# MB_dac.net
KiCad netlist of a schematic drawn in Altium Designer
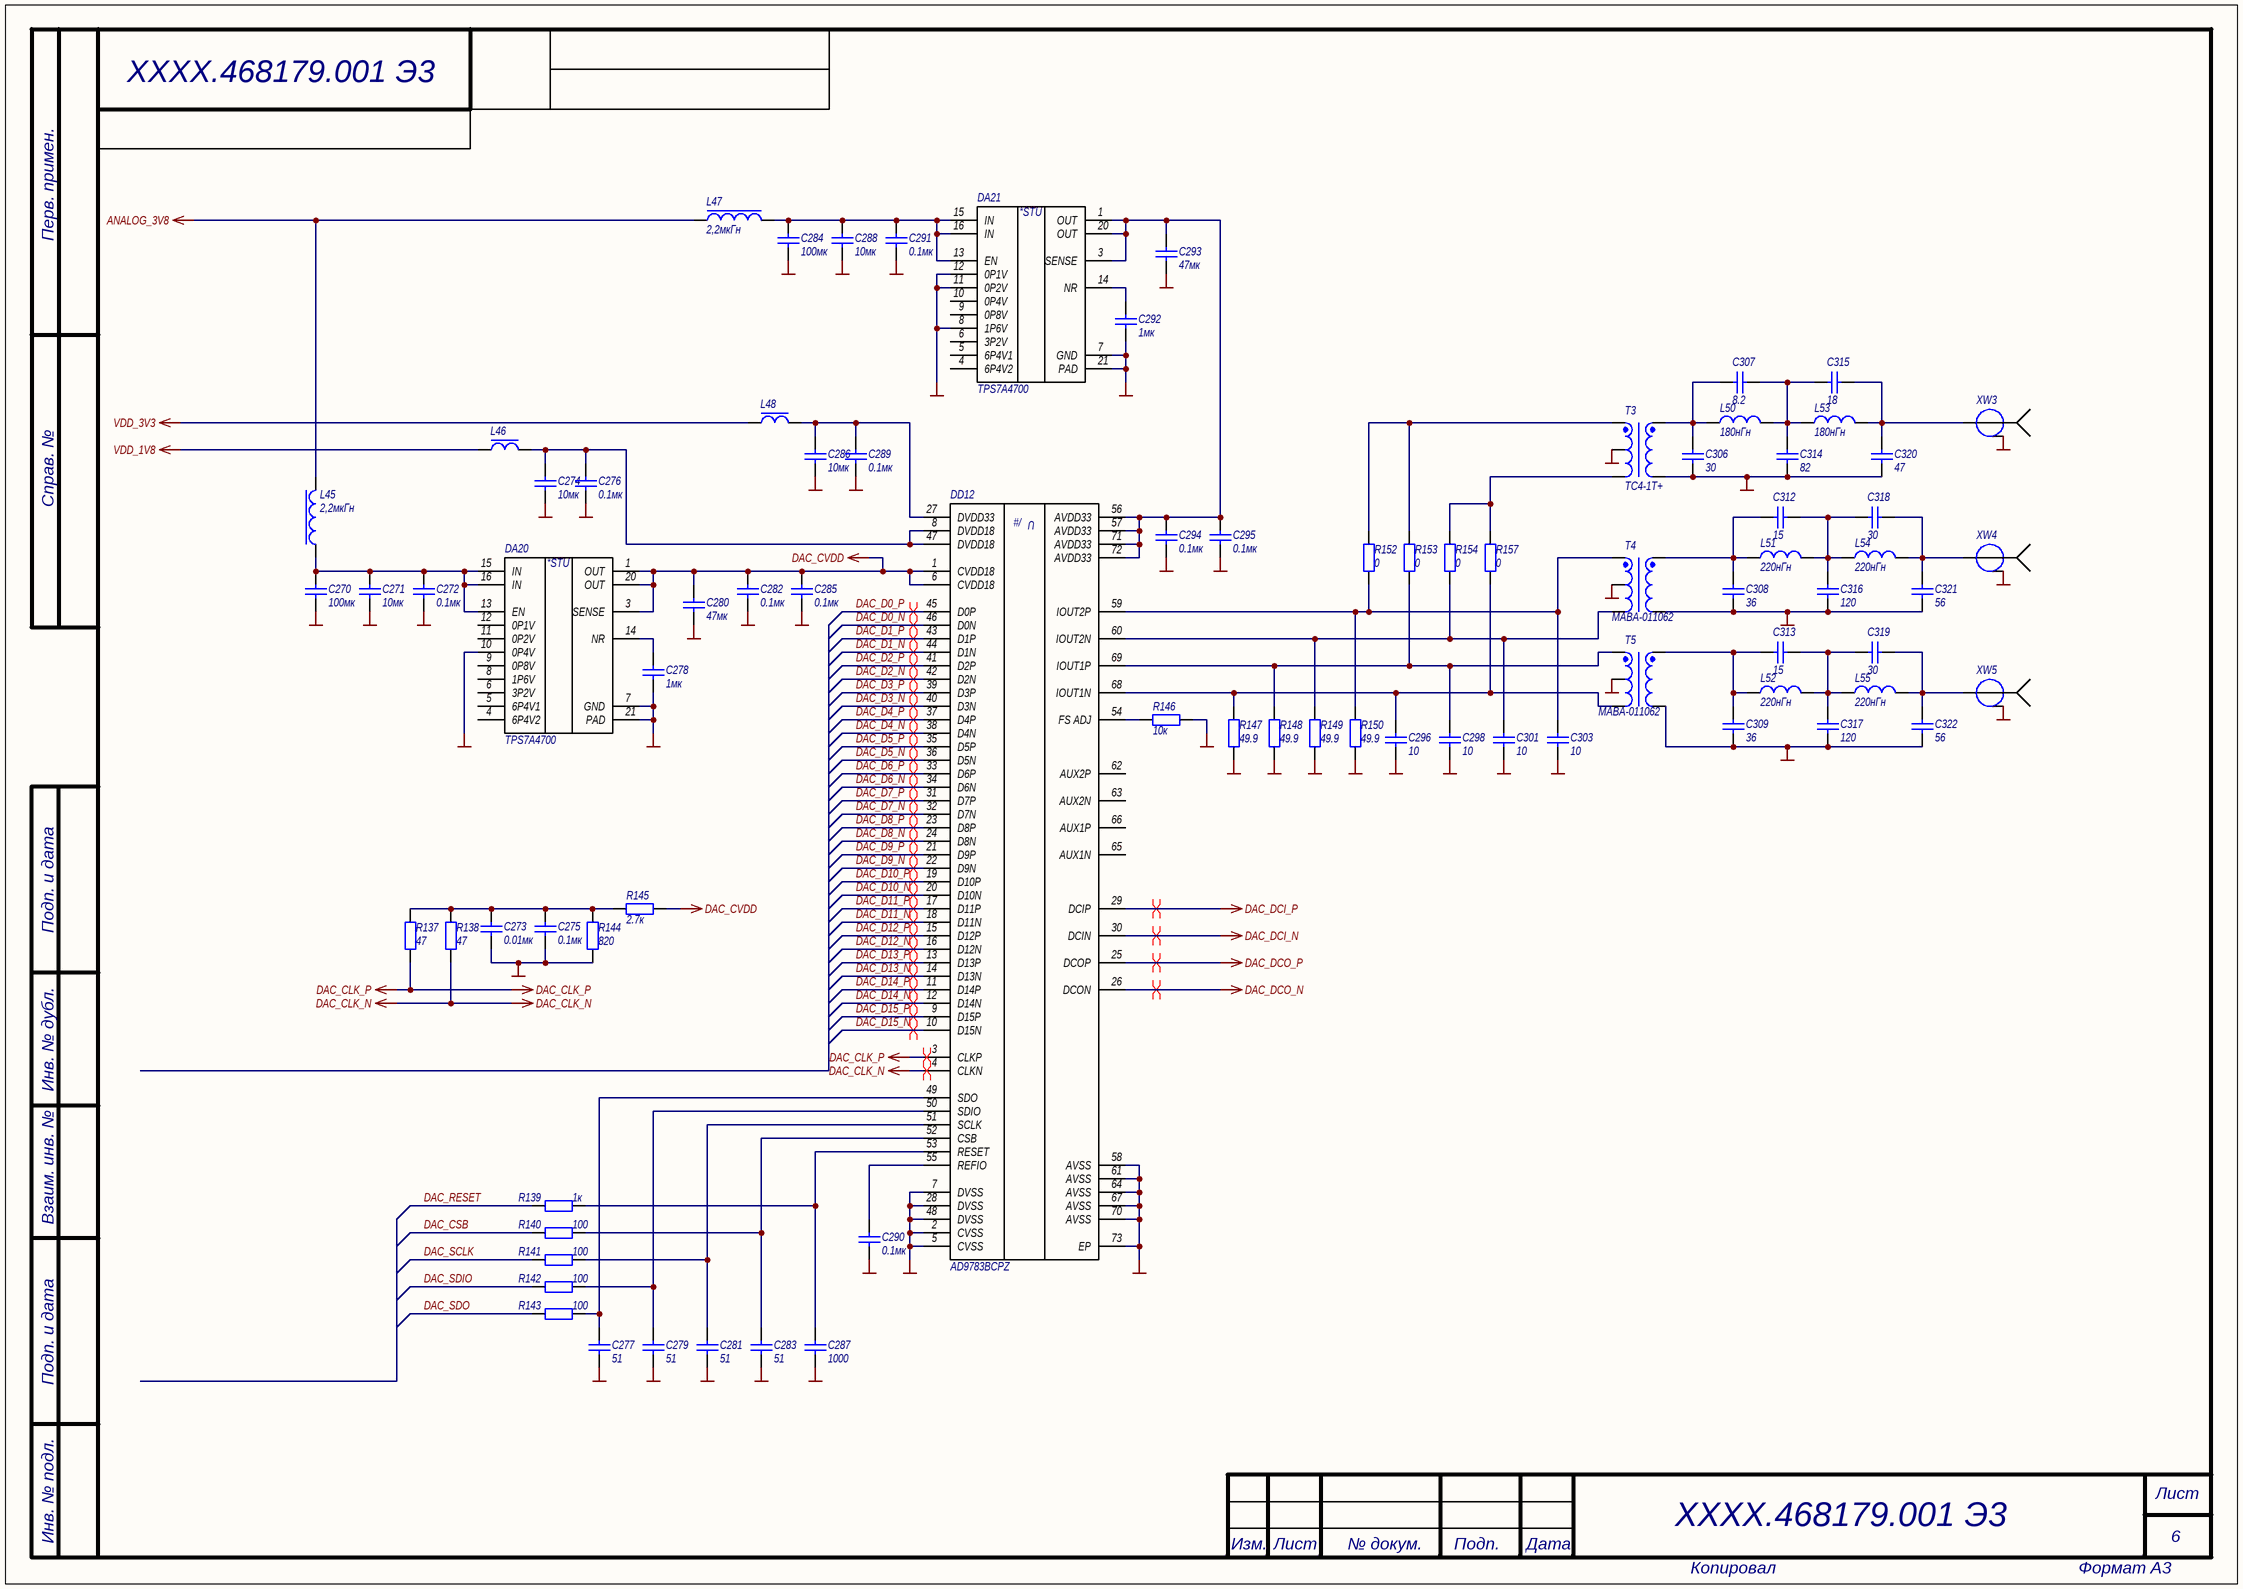
[diagram p0: MB_dac.SchDoc]

(export (version "E")
  (design (tool "Eeschema 10.0.6"))
  (components
    (comp (ref "C270")
      (value "100мк")
      (footprint "CAPC3216X19L")
      (description "Кер. ЧИП-конденсатор")
      (fields (field (name "MANUFACTURER") "Murata") (field (name "TOLERANCE") "±20%"))
      (libsource (lib "nels_caps") (part "Кер.ЧИП конд. 1206 100мкФ X5R 20% 6.3В"))
    )
    (comp (ref "C271")
      (value "10мк")
      (footprint "CAPC1608X08L")
      (description "Кер. ЧИП-конденсатор")
      (fields (field (name "MANUFACTURER") "Murata") (field (name "TOLERANCE") "±20%"))
      (libsource (lib "nels_caps") (part "Кер.ЧИП конд. 0603 10мкФ X5R 20% 6.3В"))
    )
    (comp (ref "C272")
      (value "0.1мк")
      (footprint "CAPC1005X06N")
      (description "Кер. ЧИП-конденсатор")
      (fields (field (name "TOLERANCE") "±10%"))
      (libsource (lib "nels") (part "Кер.ЧИП конд. 0402 0.1мкФ X7R 10%, 16В"))
    )
    (comp (ref "C273")
      (value "0.01мк")
      (footprint "CAPC1005X06N")
      (description "Кер. ЧИП-конденсатор")
      (fields (field (name "TOLERANCE") "±20%"))
      (libsource (lib "nels") (part "Кер.ЧИП конд. 0402 0.01мкФ X7R 10%, 50В"))
    )
    (comp (ref "C274")
      (value "10мк")
      (footprint "CAPC1608X08L")
      (description "Кер. ЧИП-конденсатор")
      (fields (field (name "MANUFACTURER") "Murata") (field (name "TOLERANCE") "±20%"))
      (libsource (lib "nels_caps") (part "Кер.ЧИП конд. 0603 10мкФ X5R 20% 6.3В"))
    )
    (comp (ref "C275")
      (value "0.1мк")
      (footprint "CAPC1005X06N")
      (description "Кер. ЧИП-конденсатор")
      (fields (field (name "TOLERANCE") "±10%"))
      (libsource (lib "nels") (part "Кер.ЧИП конд. 0402 0.1мкФ X7R 10%, 16В"))
    )
    (comp (ref "C276")
      (value "0.1мк")
      (footprint "CAPC1005X06N")
      (description "Кер. ЧИП-конденсатор")
      (fields (field (name "TOLERANCE") "±10%"))
      (libsource (lib "nels") (part "Кер.ЧИП конд. 0402 0.1мкФ X7R 10%, 16В"))
    )
    (comp (ref "C277")
      (value "51")
      (footprint "CAPC1005X06N")
      (description "Кер. ЧИП-конденсатор")
      (fields (field (name "TOLERANCE") "±5%"))
      (libsource (lib "nels") (part "Кер.ЧИП конд. 0402 51пФ NPO 5%, 50В"))
    )
    (comp (ref "C278")
      (value "1мк")
      (footprint "CAPC1005X06N")
      (description "Кер. ЧИП-конденсатор")
      (fields (field (name "TOLERANCE") "±10%"))
      (libsource (lib "nels_caps") (part "Кер.ЧИП конд. 0402 1мкФ X5R 10%, 10В"))
    )
    (comp (ref "C279")
      (value "51")
      (footprint "CAPC1005X06N")
      (description "Кер. ЧИП-конденсатор")
      (fields (field (name "TOLERANCE") "±5%"))
      (libsource (lib "nels") (part "Кер.ЧИП конд. 0402 51пФ NPO 5%, 50В"))
    )
    (comp (ref "C280")
      (value "47мк")
      (footprint "CAPC2012X12L")
      (description "Кер. ЧИП-конденсатор")
      (fields (field (name "MANUFACTURER") "Murata") (field (name "TOLERANCE") "±20%"))
      (libsource (lib "nels_caps") (part "Кер.ЧИП конд. 0805 47мкФ X5R 20% 10В"))
    )
    (comp (ref "C281")
      (value "51")
      (footprint "CAPC1005X06N")
      (description "Кер. ЧИП-конденсатор")
      (fields (field (name "TOLERANCE") "±5%"))
      (libsource (lib "nels") (part "Кер.ЧИП конд. 0402 51пФ NPO 5%, 50В"))
    )
    (comp (ref "C282")
      (value "0.1мк")
      (footprint "CAPC1005X06N")
      (description "Кер. ЧИП-конденсатор")
      (fields (field (name "TOLERANCE") "±10%"))
      (libsource (lib "nels") (part "Кер.ЧИП конд. 0402 0.1мкФ X7R 10%, 16В"))
    )
    (comp (ref "C283")
      (value "51")
      (footprint "CAPC1005X06N")
      (description "Кер. ЧИП-конденсатор")
      (fields (field (name "TOLERANCE") "±5%"))
      (libsource (lib "nels") (part "Кер.ЧИП конд. 0402 51пФ NPO 5%, 50В"))
    )
    (comp (ref "C284")
      (value "100мк")
      (footprint "CAPC3216X19L")
      (description "Кер. ЧИП-конденсатор")
      (fields (field (name "MANUFACTURER") "Murata") (field (name "TOLERANCE") "±20%"))
      (libsource (lib "nels_caps") (part "Кер.ЧИП конд. 1206 100мкФ X5R 20% 6.3В"))
    )
    (comp (ref "C285")
      (value "0.1мк")
      (footprint "CAPC1005X06N")
      (description "Кер. ЧИП-конденсатор")
      (fields (field (name "TOLERANCE") "±10%"))
      (libsource (lib "nels") (part "Кер.ЧИП конд. 0402 0.1мкФ X7R 10%, 16В"))
    )
    (comp (ref "C286")
      (value "10мк")
      (footprint "CAPC1608X08L")
      (description "Кер. ЧИП-конденсатор")
      (fields (field (name "MANUFACTURER") "Murata") (field (name "TOLERANCE") "±20%"))
      (libsource (lib "nels_caps") (part "Кер.ЧИП конд. 0603 10мкФ X5R 20% 6.3В"))
    )
    (comp (ref "C287")
      (value "1000")
      (footprint "CAPC1005X06N")
      (description "Кер. ЧИП-конденсатор")
      (fields (field (name "TOLERANCE") "±5%"))
      (libsource (lib "nels") (part "Кер.ЧИП конд. 0402 1000пФ NP0 5%, 50В"))
    )
    (comp (ref "C288")
      (value "10мк")
      (footprint "CAPC1608X08L")
      (description "Кер. ЧИП-конденсатор")
      (fields (field (name "MANUFACTURER") "Murata") (field (name "TOLERANCE") "±20%"))
      (libsource (lib "nels_caps") (part "Кер.ЧИП конд. 0603 10мкФ X5R 20% 6.3В"))
    )
    (comp (ref "C289")
      (value "0.1мк")
      (footprint "CAPC1005X06N")
      (description "Кер. ЧИП-конденсатор")
      (fields (field (name "TOLERANCE") "±10%"))
      (libsource (lib "nels") (part "Кер.ЧИП конд. 0402 0.1мкФ X7R 10%, 16В"))
    )
    (comp (ref "C290")
      (value "0.1мк")
      (footprint "CAPC1005X06N")
      (description "Кер. ЧИП-конденсатор")
      (fields (field (name "TOLERANCE") "±10%"))
      (libsource (lib "nels") (part "Кер.ЧИП конд. 0402 0.1мкФ X7R 10%, 16В"))
    )
    (comp (ref "C291")
      (value "0.1мк")
      (footprint "CAPC1005X06N")
      (description "Кер. ЧИП-конденсатор")
      (fields (field (name "TOLERANCE") "±10%"))
      (libsource (lib "nels") (part "Кер.ЧИП конд. 0402 0.1мкФ X7R 10%, 16В"))
    )
    (comp (ref "C292")
      (value "1мк")
      (footprint "CAPC1005X06N")
      (description "Кер. ЧИП-конденсатор")
      (fields (field (name "TOLERANCE") "±10%"))
      (libsource (lib "nels_caps") (part "Кер.ЧИП конд. 0402 1мкФ X5R 10%, 10В"))
    )
    (comp (ref "C293")
      (value "47мк")
      (footprint "CAPC2012X12L")
      (description "Кер. ЧИП-конденсатор")
      (fields (field (name "MANUFACTURER") "Murata") (field (name "TOLERANCE") "±20%"))
      (libsource (lib "nels_caps") (part "Кер.ЧИП конд. 0805 47мкФ X5R 20% 10В"))
    )
    (comp (ref "C294")
      (value "0.1мк")
      (footprint "CAPC1005X06N")
      (description "Кер. ЧИП-конденсатор")
      (fields (field (name "TOLERANCE") "±10%"))
      (libsource (lib "nels") (part "Кер.ЧИП конд. 0402 0.1мкФ X7R 10%, 16В"))
    )
    (comp (ref "C295")
      (value "0.1мк")
      (footprint "CAPC1005X06N")
      (description "Кер. ЧИП-конденсатор")
      (fields (field (name "TOLERANCE") "±10%"))
      (libsource (lib "nels") (part "Кер.ЧИП конд. 0402 0.1мкФ X7R 10%, 16В"))
    )
    (comp (ref "C296")
      (value "10")
      (footprint "CAPC1005X06N")
      (description "Кер. ЧИП-конденсатор")
      (fields (field (name "TOLERANCE") "±5%"))
      (libsource (lib "nels_caps") (part "Кер.ЧИП конд. 0402 10пФ NPO 5%, 50В"))
    )
    (comp (ref "C298")
      (value "10")
      (footprint "CAPC1005X06N")
      (description "Кер. ЧИП-конденсатор")
      (fields (field (name "TOLERANCE") "±5%"))
      (libsource (lib "nels_caps") (part "Кер.ЧИП конд. 0402 10пФ NPO 5%, 50В"))
    )
    (comp (ref "C301")
      (value "10")
      (footprint "CAPC1005X06N")
      (description "Кер. ЧИП-конденсатор")
      (fields (field (name "TOLERANCE") "±5%"))
      (libsource (lib "nels_caps") (part "Кер.ЧИП конд. 0402 10пФ NPO 5%, 50В"))
    )
    (comp (ref "C303")
      (value "10")
      (footprint "CAPC1005X06N")
      (description "Кер. ЧИП-конденсатор")
      (fields (field (name "TOLERANCE") "±5%"))
      (libsource (lib "nels_caps") (part "Кер.ЧИП конд. 0402 10пФ NPO 5%, 50В"))
    )
    (comp (ref "C306")
      (value "30")
      (footprint "CAPC1005X06N")
      (description "Кер. ЧИП-конденсатор")
      (fields (field (name "TOLERANCE") "±5%"))
      (libsource (lib "nels_caps") (part "Кер.ЧИП конд. 0402 30пФ NPO 5%, 50В"))
    )
    (comp (ref "C307")
      (value "8.2")
      (footprint "CAPC1005X06N")
      (description "Кер. ЧИП-конденсатор")
      (fields (field (name "TOLERANCE") "±5%"))
      (libsource (lib "nels_caps") (part "Кер.ЧИП конд. 0402 8.2пФ C0G, 50В"))
    )
    (comp (ref "C308")
      (value "36")
      (footprint "CAPC1005X06N")
      (description "Кер. ЧИП-конденсатор")
      (fields (field (name "TOLERANCE") "±5%"))
      (libsource (lib "nels") (part "Кер.ЧИП конд. 0402 36пФ NPO 5%, 50В"))
    )
    (comp (ref "C309")
      (value "36")
      (footprint "CAPC1005X06N")
      (description "Кер. ЧИП-конденсатор")
      (fields (field (name "TOLERANCE") "±5%"))
      (libsource (lib "nels") (part "Кер.ЧИП конд. 0402 36пФ NPO 5%, 50В"))
    )
    (comp (ref "C312")
      (value "15")
      (footprint "CAPC1005X06N")
      (description "Кер. ЧИП-конденсатор")
      (fields (field (name "TOLERANCE") "±5%"))
      (libsource (lib "nels") (part "Кер.ЧИП конд. 0402 15пФ NPO 5%, 50В"))
    )
    (comp (ref "C313")
      (value "15")
      (footprint "CAPC1005X06N")
      (description "Кер. ЧИП-конденсатор")
      (fields (field (name "TOLERANCE") "±5%"))
      (libsource (lib "nels") (part "Кер.ЧИП конд. 0402 15пФ NPO 5%, 50В"))
    )
    (comp (ref "C314")
      (value "82")
      (footprint "CAPC1005X06N")
      (description "Кер. ЧИП-конденсатор")
      (fields (field (name "TOLERANCE") "±5%"))
      (libsource (lib "nels_caps") (part "Кер.ЧИП конд. 0402 82пФ NPO 5%, 50В"))
    )
    (comp (ref "C315")
      (value "18")
      (footprint "CAPC1005X06N")
      (description "Кер. ЧИП-конденсатор")
      (fields (field (name "TOLERANCE") "±5%"))
      (libsource (lib "nels_caps") (part "Кер.ЧИП конд. 0402 18пФ NPO 5%, 50В"))
    )
    (comp (ref "C316")
      (value "120")
      (footprint "CAPC1005X06N")
      (description "Кер. ЧИП-конденсатор")
      (fields (field (name "TOLERANCE") "±5%"))
      (libsource (lib "nels") (part "Кер.ЧИП конд. 0402 120пФ NPO 5%, 50В"))
    )
    (comp (ref "C317")
      (value "120")
      (footprint "CAPC1005X06N")
      (description "Кер. ЧИП-конденсатор")
      (fields (field (name "TOLERANCE") "±5%"))
      (libsource (lib "nels") (part "Кер.ЧИП конд. 0402 120пФ NPO 5%, 50В"))
    )
    (comp (ref "C318")
      (value "30")
      (footprint "CAPC1005X06N")
      (description "Кер. ЧИП-конденсатор")
      (fields (field (name "TOLERANCE") "±5%"))
      (libsource (lib "nels") (part "Кер.ЧИП конд. 0402 30пФ NPO 5%, 50В"))
    )
    (comp (ref "C319")
      (value "30")
      (footprint "CAPC1005X06N")
      (description "Кер. ЧИП-конденсатор")
      (fields (field (name "TOLERANCE") "±5%"))
      (libsource (lib "nels") (part "Кер.ЧИП конд. 0402 30пФ NPO 5%, 50В"))
    )
    (comp (ref "C320")
      (value "47")
      (footprint "CAPC1005X06N")
      (description "Кер. ЧИП-конденсатор")
      (fields (field (name "TOLERANCE") "±5%"))
      (libsource (lib "nels_caps") (part "Кер.ЧИП конд. 0402 47пФ NPO 5%, 50В"))
    )
    (comp (ref "C321")
      (value "56")
      (footprint "CAPC1005X06N")
      (description "Кер. ЧИП-конденсатор")
      (fields (field (name "TOLERANCE") "±5%"))
      (libsource (lib "nels") (part "Кер.ЧИП конд. 0402 56пФ NPO 5%, 50В"))
    )
    (comp (ref "C322")
      (value "56")
      (footprint "CAPC1005X06N")
      (description "Кер. ЧИП-конденсатор")
      (fields (field (name "TOLERANCE") "±5%"))
      (libsource (lib "nels") (part "Кер.ЧИП конд. 0402 56пФ NPO 5%, 50В"))
    )
    (comp (ref "DA20")
      (value "TPS7A4700")
      (footprint "QFN65P500X500X100_HS-21L")
      (description "36-V, 1-A, 4-µVRMS, RF LDO Voltage Regulator")
      (fields (field (name "MANUFACTURER") "TI"))
      (libsource (lib "nels_chip") (part "Микросхема TPS7A4700RGW"))
    )
    (comp (ref "DA21")
      (value "TPS7A4700")
      (footprint "QFN65P500X500X100_HS-21L")
      (description "36-V, 1-A, 4-µVRMS, RF LDO Voltage Regulator")
      (fields (field (name "MANUFACTURER") "TI"))
      (libsource (lib "nels_chip") (part "Микросхема TPS7A4700RGW"))
    )
    (comp (ref "DD12")
      (value "AD9783BCPZ")
      (footprint "LFCSP_VQ_72")
      (description "Dual 12-/14-/16-Bit, LVDS Interface, 500 MSPS DACs")
      (fields (field (name "MANUFACTURER") "AD"))
      (libsource (lib "nels") (part "Микросхема AD9783BCPZ"))
    )
    (comp (ref "L45")
      (value "2,2мкГн")
      (footprint "CSAB0420")
      (description "Molding Power Choke")
      (fields
        (field (name "MANUFACTURER") "Vishay")
        (field (name "MANUFACTURERPARTNUMBER") "IHLP1616ABER1R0M11")
      )
      (libsource (lib "nels_ind") (part "ЧИП индуктивность CSAB0420-2R2M"))
    )
    (comp (ref "L46")
      (value "BLM18PG121SN1D")
      (footprint "INDC1608X08L")
      (description "SMD EMI Suppression Filter EMIFIL")
      (fields (field (name "MANUFACTURER") "Murata"))
      (libsource (lib "nels_ind") (part "ЧИП дроссель 0603 BLM18PG121SN1D"))
    )
    (comp (ref "L47")
      (value "2,2мкГн")
      (footprint "CSAB0420")
      (description "Molding Power Choke")
      (fields
        (field (name "MANUFACTURER") "Vishay")
        (field (name "MANUFACTURERPARTNUMBER") "IHLP1616ABER1R0M11")
      )
      (libsource (lib "nels_ind") (part "ЧИП индуктивность CSAB0420-2R2M"))
    )
    (comp (ref "L48")
      (value "BLM18PG121SN1D")
      (footprint "INDC1608X08L")
      (description "SMD EMI Suppression Filter EMIFIL")
      (fields (field (name "MANUFACTURER") "Murata"))
      (libsource (lib "nels_ind") (part "ЧИП дроссель 0603 BLM18PG121SN1D"))
    )
    (comp (ref "L50")
      (value "180нГн")
      (footprint "INDC0805CS")
      (libsource (lib "nels_ind") (part "ЧИП индуктивность 0805CS-181XGL"))
    )
    (comp (ref "L51")
      (value "220нГн")
      (footprint "INDC0805CS")
      (libsource (lib "nels") (part "ЧИП индуктивность 0805CS-221XGL"))
    )
    (comp (ref "L52")
      (value "220нГн")
      (footprint "INDC0805CS")
      (libsource (lib "nels") (part "ЧИП индуктивность 0805CS-221XGL"))
    )
    (comp (ref "L53")
      (value "180нГн")
      (footprint "INDC0805CS")
      (libsource (lib "nels_ind") (part "ЧИП индуктивность 0805CS-181XGL"))
    )
    (comp (ref "L54")
      (value "220нГн")
      (footprint "INDC0805CS")
      (libsource (lib "nels") (part "ЧИП индуктивность 0805CS-221XGL"))
    )
    (comp (ref "L55")
      (value "220нГн")
      (footprint "INDC0805CS")
      (libsource (lib "nels") (part "ЧИП индуктивность 0805CS-221XGL"))
    )
    (comp (ref "R137")
      (value "47")
      (footprint "RESC1005X06N")
      (description "ЧИП-резистор")
      (fields (field (name "TOLERANCE") "±5%"))
      (libsource (lib "nels") (part "Чип резистор 0402 47 Ом, 5%"))
    )
    (comp (ref "R138")
      (value "47")
      (footprint "RESC1005X06N")
      (description "ЧИП-резистор")
      (fields (field (name "TOLERANCE") "±5%"))
      (libsource (lib "nels") (part "Чип резистор 0402 47 Ом, 5%"))
    )
    (comp (ref "R139")
      (value "1к")
      (footprint "RESC1005X06N")
      (description "ЧИП-резистор")
      (fields (field (name "TOLERANCE") "±5%"))
      (libsource (lib "nels") (part "Чип резистор 0402 1 кОм, 5%"))
    )
    (comp (ref "R140")
      (value "100")
      (footprint "RESC1005X06N")
      (description "ЧИП-резистор")
      (fields (field (name "TOLERANCE") "±5%"))
      (libsource (lib "nels") (part "Чип резистор 0402 100 Ом, 5%"))
    )
    (comp (ref "R141")
      (value "100")
      (footprint "RESC1005X06N")
      (description "ЧИП-резистор")
      (fields (field (name "TOLERANCE") "±5%"))
      (libsource (lib "nels") (part "Чип резистор 0402 100 Ом, 5%"))
    )
    (comp (ref "R142")
      (value "100")
      (footprint "RESC1005X06N")
      (description "ЧИП-резистор")
      (fields (field (name "TOLERANCE") "±5%"))
      (libsource (lib "nels") (part "Чип резистор 0402 100 Ом, 5%"))
    )
    (comp (ref "R143")
      (value "100")
      (footprint "RESC1005X06N")
      (description "ЧИП-резистор")
      (fields (field (name "TOLERANCE") "±5%"))
      (libsource (lib "nels") (part "Чип резистор 0402 100 Ом, 5%"))
    )
    (comp (ref "R144")
      (value "820")
      (footprint "RESC1005X06N")
      (description "ЧИП-резистор")
      (fields (field (name "TOLERANCE") "±5%"))
      (libsource (lib "nels") (part "Чип резистор 0402 820 Ом, 5%"))
    )
    (comp (ref "R145")
      (value "2.7к")
      (footprint "RESC1005X06N")
      (description "ЧИП-резистор")
      (fields (field (name "TOLERANCE") "±5%") (field (name "PUBLISHER") "Altium Limited"))
      (libsource (lib "nels") (part "Чип резистор 0402 2.7 кОм, 5%"))
    )
    (comp (ref "R146")
      (value "10к")
      (footprint "RESC1005X06N")
      (description "ЧИП-резистор")
      (fields (field (name "TOLERANCE") "±5%"))
      (libsource (lib "nels") (part "Чип резистор 0402 10 кОм, 5%"))
    )
    (comp (ref "R147")
      (value "49.9")
      (footprint "RESC1005X06N")
      (description "ЧИП-резистор")
      (fields (field (name "TOLERANCE") "±1%"))
      (libsource (lib "nels") (part "Чип резистор 0402 49,9 Ом, 1%"))
    )
    (comp (ref "R148")
      (value "49.9")
      (footprint "RESC1005X06N")
      (description "ЧИП-резистор")
      (fields (field (name "TOLERANCE") "±1%"))
      (libsource (lib "nels") (part "Чип резистор 0402 49,9 Ом, 1%"))
    )
    (comp (ref "R149")
      (value "49.9")
      (footprint "RESC1005X06N")
      (description "ЧИП-резистор")
      (fields (field (name "TOLERANCE") "±1%"))
      (libsource (lib "nels") (part "Чип резистор 0402 49,9 Ом, 1%"))
    )
    (comp (ref "R150")
      (value "49.9")
      (footprint "RESC1005X06N")
      (description "ЧИП-резистор")
      (fields (field (name "TOLERANCE") "±1%"))
      (libsource (lib "nels") (part "Чип резистор 0402 49,9 Ом, 1%"))
    )
    (comp (ref "R152")
      (value "0")
      (footprint "RESC1005X06N")
      (description "ЧИП-резистор")
      (fields (field (name "TOLERANCE") "±5%"))
      (libsource (lib "nels_res") (part "Чип резистор 0402 0 Ом"))
    )
    (comp (ref "R153")
      (value "0")
      (footprint "RESC1005X06N")
      (description "ЧИП-резистор")
      (fields (field (name "TOLERANCE") "±5%"))
      (libsource (lib "nels_res") (part "Чип резистор 0402 0 Ом"))
    )
    (comp (ref "R154")
      (value "0")
      (footprint "RESC1005X06N")
      (description "ЧИП-резистор")
      (fields (field (name "TOLERANCE") "±5%"))
      (libsource (lib "nels_res") (part "Чип резистор 0402 0 Ом"))
    )
    (comp (ref "R157")
      (value "0")
      (footprint "RESC1005X06N")
      (description "ЧИП-резистор")
      (fields (field (name "TOLERANCE") "±5%"))
      (libsource (lib "nels_res") (part "Чип резистор 0402 0 Ом"))
    )
    (comp (ref "T3")
      (value "TC4-1T+")
      (footprint "SM-22 package")
      (description "RF Transformer 50Ω 0.5 to 300 MHz 1:4")
      (fields (field (name "MANUFACTURER") "minicircuits") (field (name "MANUFACTURERPARTNUMBER") "ADT2-1T+"))
      (libsource (lib "nels_ind") (part "ЧИП трансформатор TC4-1T+"))
    )
    (comp (ref "T4")
      (value "MABA-011062")
      (footprint "SM-22 package")
      (description "1:2 Step up Flux Coupled Balun Transformer 1 – 300 MHz")
      (fields (field (name "MANUFACTURER") "MACOM"))
      (libsource (lib "nels") (part "ЧИП трансформатор MABA-011062"))
    )
    (comp (ref "T5")
      (value "MABA-011062")
      (footprint "SM-22 package")
      (description "1:2 Step up Flux Coupled Balun Transformer 1 – 300 MHz")
      (fields (field (name "MANUFACTURER") "MACOM"))
      (libsource (lib "nels") (part "ЧИП трансформатор MABA-011062"))
    )
    (comp (ref "XW3")
      (value "SMA-JR")
      (footprint "SMA-JR")
      (description "SMA-JR Разъем SMA гнездо на плату, прямой угол")
      (libsource (lib "nels_conn") (part "Соединитель коаксиальный SMA-JR"))
    )
    (comp (ref "XW4")
      (value "SMA-JR")
      (footprint "SMA-JR")
      (description "SMA-JR Разъем SMA гнездо на плату, прямой угол")
      (libsource (lib "nels_conn") (part "Соединитель коаксиальный SMA-JR"))
    )
    (comp (ref "XW5")
      (value "SMA-JR")
      (footprint "SMA-JR")
      (description "SMA-JR Разъем SMA гнездо на плату, прямой угол")
      (libsource (lib "nels_conn") (part "Соединитель коаксиальный SMA-JR"))
    )
  )
  (nets
    (net (code "1") (name "/DAC_CSB") (class "Default")
      (node (ref "R140") (pin "1") (pinfunction "1_1") (pintype "passive"))
    )
    (net (code "2") (name "/DAC_D0_N") (class "Default")
      (node (ref "DD12") (pin "46") (pinfunction "D0N_46") (pintype "passive"))
    )
    (net (code "3") (name "/DAC_D0_P") (class "Default")
      (node (ref "DD12") (pin "45") (pinfunction "D0P_45") (pintype "passive"))
    )
    (net (code "4") (name "/DAC_D1_N") (class "Default")
      (node (ref "DD12") (pin "44") (pinfunction "D1N_44") (pintype "passive"))
    )
    (net (code "5") (name "/DAC_D1_P") (class "Default")
      (node (ref "DD12") (pin "43") (pinfunction "D1P_43") (pintype "passive"))
    )
    (net (code "6") (name "/DAC_D2_N") (class "Default")
      (node (ref "DD12") (pin "42") (pinfunction "D2N_42") (pintype "passive"))
    )
    (net (code "7") (name "/DAC_D2_P") (class "Default")
      (node (ref "DD12") (pin "41") (pinfunction "D2P_41") (pintype "passive"))
    )
    (net (code "8") (name "/DAC_D3_N") (class "Default")
      (node (ref "DD12") (pin "40") (pinfunction "D3N_40") (pintype "passive"))
    )
    (net (code "9") (name "/DAC_D3_P") (class "Default")
      (node (ref "DD12") (pin "39") (pinfunction "D3P_39") (pintype "passive"))
    )
    (net (code "10") (name "/DAC_D4_N") (class "Default")
      (node (ref "DD12") (pin "38") (pinfunction "D4N_38") (pintype "passive"))
    )
    (net (code "11") (name "/DAC_D4_P") (class "Default")
      (node (ref "DD12") (pin "37") (pinfunction "D4P_37") (pintype "passive"))
    )
    (net (code "12") (name "/DAC_D5_N") (class "Default")
      (node (ref "DD12") (pin "36") (pinfunction "D5N_36") (pintype "passive"))
    )
    (net (code "13") (name "/DAC_D5_P") (class "Default")
      (node (ref "DD12") (pin "35") (pinfunction "D5P_35") (pintype "passive"))
    )
    (net (code "14") (name "/DAC_D6_N") (class "Default")
      (node (ref "DD12") (pin "34") (pinfunction "D6N_34") (pintype "passive"))
    )
    (net (code "15") (name "/DAC_D6_P") (class "Default")
      (node (ref "DD12") (pin "33") (pinfunction "D6P_33") (pintype "passive"))
    )
    (net (code "16") (name "/DAC_D7_N") (class "Default")
      (node (ref "DD12") (pin "32") (pinfunction "D7N_32") (pintype "passive"))
    )
    (net (code "17") (name "/DAC_D7_P") (class "Default")
      (node (ref "DD12") (pin "31") (pinfunction "D7P_31") (pintype "passive"))
    )
    (net (code "18") (name "/DAC_D8_N") (class "Default")
      (node (ref "DD12") (pin "24") (pinfunction "D8N_24") (pintype "passive"))
    )
    (net (code "19") (name "/DAC_D8_P") (class "Default")
      (node (ref "DD12") (pin "23") (pinfunction "D8P_23") (pintype "passive"))
    )
    (net (code "20") (name "/DAC_D9_N") (class "Default")
      (node (ref "DD12") (pin "22") (pinfunction "D9N_22") (pintype "passive"))
    )
    (net (code "21") (name "/DAC_D9_P") (class "Default")
      (node (ref "DD12") (pin "21") (pinfunction "D9P_21") (pintype "passive"))
    )
    (net (code "22") (name "/DAC_D10_N") (class "Default")
      (node (ref "DD12") (pin "20") (pinfunction "D10N_20") (pintype "passive"))
    )
    (net (code "23") (name "/DAC_D10_P") (class "Default")
      (node (ref "DD12") (pin "19") (pinfunction "D10P_19") (pintype "passive"))
    )
    (net (code "24") (name "/DAC_D11_N") (class "Default")
      (node (ref "DD12") (pin "18") (pinfunction "D11N_18") (pintype "passive"))
    )
    (net (code "25") (name "/DAC_D11_P") (class "Default")
      (node (ref "DD12") (pin "17") (pinfunction "D11P_17") (pintype "passive"))
    )
    (net (code "26") (name "/DAC_D12_N") (class "Default")
      (node (ref "DD12") (pin "16") (pinfunction "D12N_16") (pintype "passive"))
    )
    (net (code "27") (name "/DAC_D12_P") (class "Default")
      (node (ref "DD12") (pin "15") (pinfunction "D12P_15") (pintype "passive"))
    )
    (net (code "28") (name "/DAC_D13_N") (class "Default")
      (node (ref "DD12") (pin "14") (pinfunction "D13N_14") (pintype "passive"))
    )
    (net (code "29") (name "/DAC_D13_P") (class "Default")
      (node (ref "DD12") (pin "13") (pinfunction "D13P_13") (pintype "passive"))
    )
    (net (code "30") (name "/DAC_D14_N") (class "Default")
      (node (ref "DD12") (pin "12") (pinfunction "D14N_12") (pintype "passive"))
    )
    (net (code "31") (name "/DAC_D14_P") (class "Default")
      (node (ref "DD12") (pin "11") (pinfunction "D14P_11") (pintype "passive"))
    )
    (net (code "32") (name "/DAC_D15_N") (class "Default")
      (node (ref "DD12") (pin "10") (pinfunction "D15N_10") (pintype "passive"))
    )
    (net (code "33") (name "/DAC_D15_P") (class "Default")
      (node (ref "DD12") (pin "9") (pinfunction "D15P_9") (pintype "passive"))
    )
    (net (code "34") (name "/DAC_RESET") (class "Default")
      (node (ref "R139") (pin "1") (pinfunction "1_1") (pintype "passive"))
    )
    (net (code "35") (name "/DAC_SCLK") (class "Default")
      (node (ref "R141") (pin "1") (pinfunction "1_1") (pintype "passive"))
    )
    (net (code "36") (name "/DAC_SDIO") (class "Default")
      (node (ref "R142") (pin "1") (pinfunction "1_1") (pintype "passive"))
    )
    (net (code "37") (name "/DAC_SDO") (class "Default")
      (node (ref "R143") (pin "1") (pinfunction "1_1") (pintype "passive"))
    )
    (net (code "38") (name "ANALOG_3V8") (class "Default")
      (node (ref "L45") (pin "2") (pinfunction "2_2") (pintype "passive"))
      (node (ref "L47") (pin "1") (pinfunction "1_1") (pintype "passive"))
    )
    (net (code "39") (name "DAC_CLK_N") (class "Default")
      (node (ref "DD12") (pin "4") (pinfunction "CLKN_4") (pintype "passive"))
      (node (ref "R138") (pin "2") (pinfunction "2_2") (pintype "passive"))
    )
    (net (code "40") (name "DAC_CLK_P") (class "Default")
      (node (ref "DD12") (pin "3") (pinfunction "CLKP_3") (pintype "passive"))
      (node (ref "R137") (pin "2") (pinfunction "2_2") (pintype "passive"))
    )
    (net (code "41") (name "DAC_CVDD") (class "Default")
      (node (ref "C280") (pin "2") (pinfunction "2_2") (pintype "passive"))
      (node (ref "C282") (pin "2") (pinfunction "2_2") (pintype "passive"))
      (node (ref "C285") (pin "2") (pinfunction "2_2") (pintype "passive"))
      (node (ref "DA20") (pin "1") (pinfunction "OUT_1") (pintype "passive"))
      (node (ref "DA20") (pin "20") (pinfunction "OUT_20") (pintype "passive"))
      (node (ref "DA20") (pin "3") (pinfunction "SENSE_3") (pintype "passive"))
      (node (ref "DD12") (pin "1") (pinfunction "CVDD18_1") (pintype "passive"))
      (node (ref "DD12") (pin "6") (pinfunction "CVDD18_6") (pintype "passive"))
      (node (ref "R145") (pin "2") (pinfunction "2_2") (pintype "passive"))
    )
    (net (code "42") (name "DAC_DCI_N") (class "Default")
      (node (ref "DD12") (pin "30") (pinfunction "DCIN_30") (pintype "passive"))
    )
    (net (code "43") (name "DAC_DCI_P") (class "Default")
      (node (ref "DD12") (pin "29") (pinfunction "DCIP_29") (pintype "passive"))
    )
    (net (code "44") (name "DAC_DCO_N") (class "Default")
      (node (ref "DD12") (pin "26") (pinfunction "DCON_26") (pintype "passive"))
    )
    (net (code "45") (name "DAC_DCO_P") (class "Default")
      (node (ref "DD12") (pin "25") (pinfunction "DCOP_25") (pintype "passive"))
    )
    (net (code "46") (name "GND") (class "Default")
      (node (ref "C270") (pin "1") (pinfunction "1_1") (pintype "passive"))
      (node (ref "C271") (pin "1") (pinfunction "1_1") (pintype "passive"))
      (node (ref "C272") (pin "1") (pinfunction "1_1") (pintype "passive"))
      (node (ref "C273") (pin "1") (pinfunction "1_1") (pintype "passive"))
      (node (ref "C274") (pin "1") (pinfunction "1_1") (pintype "passive"))
      (node (ref "C275") (pin "1") (pinfunction "1_1") (pintype "passive"))
      (node (ref "C276") (pin "1") (pinfunction "1_1") (pintype "passive"))
      (node (ref "C277") (pin "1") (pinfunction "1_1") (pintype "passive"))
      (node (ref "C278") (pin "1") (pinfunction "1_1") (pintype "passive"))
      (node (ref "C279") (pin "1") (pinfunction "1_1") (pintype "passive"))
      (node (ref "C280") (pin "1") (pinfunction "1_1") (pintype "passive"))
      (node (ref "C281") (pin "1") (pinfunction "1_1") (pintype "passive"))
      (node (ref "C282") (pin "1") (pinfunction "1_1") (pintype "passive"))
      (node (ref "C283") (pin "1") (pinfunction "1_1") (pintype "passive"))
      (node (ref "C284") (pin "1") (pinfunction "1_1") (pintype "passive"))
      (node (ref "C285") (pin "1") (pinfunction "1_1") (pintype "passive"))
      (node (ref "C286") (pin "1") (pinfunction "1_1") (pintype "passive"))
      (node (ref "C287") (pin "1") (pinfunction "1_1") (pintype "passive"))
      (node (ref "C288") (pin "1") (pinfunction "1_1") (pintype "passive"))
      (node (ref "C289") (pin "1") (pinfunction "1_1") (pintype "passive"))
      (node (ref "C290") (pin "1") (pinfunction "1_1") (pintype "passive"))
      (node (ref "C291") (pin "1") (pinfunction "1_1") (pintype "passive"))
      (node (ref "C292") (pin "1") (pinfunction "1_1") (pintype "passive"))
      (node (ref "C293") (pin "1") (pinfunction "1_1") (pintype "passive"))
      (node (ref "C294") (pin "1") (pinfunction "1_1") (pintype "passive"))
      (node (ref "C295") (pin "1") (pinfunction "1_1") (pintype "passive"))
      (node (ref "C296") (pin "1") (pinfunction "1_1") (pintype "passive"))
      (node (ref "C298") (pin "1") (pinfunction "1_1") (pintype "passive"))
      (node (ref "C301") (pin "1") (pinfunction "1_1") (pintype "passive"))
      (node (ref "C303") (pin "1") (pinfunction "1_1") (pintype "passive"))
      (node (ref "C306") (pin "1") (pinfunction "1_1") (pintype "passive"))
      (node (ref "C308") (pin "1") (pinfunction "1_1") (pintype "passive"))
      (node (ref "C309") (pin "1") (pinfunction "1_1") (pintype "passive"))
      (node (ref "C314") (pin "1") (pinfunction "1_1") (pintype "passive"))
      (node (ref "C316") (pin "1") (pinfunction "1_1") (pintype "passive"))
      (node (ref "C317") (pin "1") (pinfunction "1_1") (pintype "passive"))
      (node (ref "C320") (pin "1") (pinfunction "1_1") (pintype "passive"))
      (node (ref "C321") (pin "1") (pinfunction "1_1") (pintype "passive"))
      (node (ref "C322") (pin "1") (pinfunction "1_1") (pintype "passive"))
      (node (ref "DA20") (pin "10") (pinfunction "0P4V_10") (pintype "passive"))
      (node (ref "DA20") (pin "21") (pinfunction "PAD_21") (pintype "passive"))
      (node (ref "DA20") (pin "7") (pinfunction "GND_7") (pintype "passive"))
      (node (ref "DA21") (pin "11") (pinfunction "0P2V_11") (pintype "passive"))
      (node (ref "DA21") (pin "12") (pinfunction "0P1V_12") (pintype "passive"))
      (node (ref "DA21") (pin "21") (pinfunction "PAD_21") (pintype "passive"))
      (node (ref "DA21") (pin "7") (pinfunction "GND_7") (pintype "passive"))
      (node (ref "DA21") (pin "8") (pinfunction "1P6V_8") (pintype "passive"))
      (node (ref "DD12") (pin "2") (pinfunction "CVSS_2") (pintype "passive"))
      (node (ref "DD12") (pin "28") (pinfunction "DVSS_28") (pintype "passive"))
      (node (ref "DD12") (pin "48") (pinfunction "DVSS_48") (pintype "passive"))
      (node (ref "DD12") (pin "5") (pinfunction "CVSS_5") (pintype "passive"))
      (node (ref "DD12") (pin "58") (pinfunction "AVSS_58") (pintype "passive"))
      (node (ref "DD12") (pin "61") (pinfunction "AVSS_61") (pintype "passive"))
      (node (ref "DD12") (pin "64") (pinfunction "AVSS_64") (pintype "passive"))
      (node (ref "DD12") (pin "67") (pinfunction "AVSS_67") (pintype "passive"))
      (node (ref "DD12") (pin "7") (pinfunction "DVSS_7") (pintype "passive"))
      (node (ref "DD12") (pin "70") (pinfunction "AVSS_70") (pintype "passive"))
      (node (ref "DD12") (pin "73") (pinfunction "EP_73") (pintype "passive"))
      (node (ref "R144") (pin "2") (pinfunction "2_2") (pintype "passive"))
      (node (ref "R146") (pin "2") (pinfunction "2_2") (pintype "passive"))
      (node (ref "R147") (pin "2") (pinfunction "2_2") (pintype "passive"))
      (node (ref "R148") (pin "2") (pinfunction "2_2") (pintype "passive"))
      (node (ref "R149") (pin "2") (pinfunction "2_2") (pintype "passive"))
      (node (ref "R150") (pin "2") (pinfunction "2_2") (pintype "passive"))
      (node (ref "T3") (pin "2") (pinfunction "SECONARY_CT_2") (pintype "passive"))
      (node (ref "T3") (pin "4") (pinfunction "PRIMARY_4") (pintype "passive"))
      (node (ref "T4") (pin "2") (pinfunction "SECONARY_CT_2") (pintype "passive"))
      (node (ref "T4") (pin "4") (pinfunction "PRIMARY_4") (pintype "passive"))
      (node (ref "T5") (pin "2") (pinfunction "SECONARY_CT_2") (pintype "passive"))
      (node (ref "T5") (pin "4") (pinfunction "PRIMARY_4") (pintype "passive"))
      (node (ref "XW3") (pin "2") (pinfunction "2_2") (pintype "passive"))
      (node (ref "XW4") (pin "2") (pinfunction "2_2") (pintype "passive"))
      (node (ref "XW5") (pin "2") (pinfunction "2_2") (pintype "passive"))
    )
    (net (code "47") (name "Net-(C273-Pad2)") (class "Default")
      (node (ref "C273") (pin "2") (pinfunction "2_2") (pintype "passive"))
      (node (ref "C275") (pin "2") (pinfunction "2_2") (pintype "passive"))
      (node (ref "R137") (pin "1") (pinfunction "1_1") (pintype "passive"))
      (node (ref "R138") (pin "1") (pinfunction "1_1") (pintype "passive"))
      (node (ref "R144") (pin "1") (pinfunction "1_1") (pintype "passive"))
      (node (ref "R145") (pin "1") (pinfunction "1_1") (pintype "passive"))
    )
    (net (code "48") (name "Net-(C274-Pad2)") (class "Default")
      (node (ref "C274") (pin "2") (pinfunction "2_2") (pintype "passive"))
      (node (ref "C276") (pin "2") (pinfunction "2_2") (pintype "passive"))
      (node (ref "DD12") (pin "47") (pinfunction "DVDD18_47") (pintype "passive"))
      (node (ref "DD12") (pin "8") (pinfunction "DVDD18_8") (pintype "passive"))
      (node (ref "L46") (pin "2") (pinfunction "2_2") (pintype "passive"))
    )
    (net (code "49") (name "Net-(C307-Pad1)") (class "Default")
      (node (ref "C307") (pin "1") (pinfunction "1_1") (pintype "passive"))
      (node (ref "C314") (pin "2") (pinfunction "2_2") (pintype "passive"))
      (node (ref "C315") (pin "2") (pinfunction "2_2") (pintype "passive"))
      (node (ref "L50") (pin "2") (pinfunction "2_2") (pintype "passive"))
      (node (ref "L53") (pin "1") (pinfunction "1_1") (pintype "passive"))
    )
    (net (code "50") (name "Net-(C312-Pad1)") (class "Default")
      (node (ref "C312") (pin "1") (pinfunction "1_1") (pintype "passive"))
      (node (ref "C316") (pin "2") (pinfunction "2_2") (pintype "passive"))
      (node (ref "C318") (pin "2") (pinfunction "2_2") (pintype "passive"))
      (node (ref "L51") (pin "2") (pinfunction "2_2") (pintype "passive"))
      (node (ref "L54") (pin "1") (pinfunction "1_1") (pintype "passive"))
    )
    (net (code "51") (name "Net-(C313-Pad1)") (class "Default")
      (node (ref "C313") (pin "1") (pinfunction "1_1") (pintype "passive"))
      (node (ref "C317") (pin "2") (pinfunction "2_2") (pintype "passive"))
      (node (ref "C319") (pin "2") (pinfunction "2_2") (pintype "passive"))
      (node (ref "L52") (pin "2") (pinfunction "2_2") (pintype "passive"))
      (node (ref "L55") (pin "1") (pinfunction "1_1") (pintype "passive"))
    )
    (net (code "52") (name "Net-(C315-Pad1)") (class "Default")
      (node (ref "C315") (pin "1") (pinfunction "1_1") (pintype "passive"))
      (node (ref "C320") (pin "2") (pinfunction "2_2") (pintype "passive"))
      (node (ref "L53") (pin "2") (pinfunction "2_2") (pintype "passive"))
      (node (ref "XW3") (pin "1") (pinfunction "1_1") (pintype "passive"))
    )
    (net (code "53") (name "Net-(C318-Pad1)") (class "Default")
      (node (ref "C318") (pin "1") (pinfunction "1_1") (pintype "passive"))
      (node (ref "C321") (pin "2") (pinfunction "2_2") (pintype "passive"))
      (node (ref "L54") (pin "2") (pinfunction "2_2") (pintype "passive"))
      (node (ref "XW4") (pin "1") (pinfunction "1_1") (pintype "passive"))
    )
    (net (code "54") (name "Net-(C319-Pad1)") (class "Default")
      (node (ref "C319") (pin "1") (pinfunction "1_1") (pintype "passive"))
      (node (ref "C322") (pin "2") (pinfunction "2_2") (pintype "passive"))
      (node (ref "L55") (pin "2") (pinfunction "2_2") (pintype "passive"))
      (node (ref "XW5") (pin "1") (pinfunction "1_1") (pintype "passive"))
    )
    (net (code "55") (name "Net-(DA20-EN)") (class "Default")
      (node (ref "C270") (pin "2") (pinfunction "2_2") (pintype "passive"))
      (node (ref "C271") (pin "2") (pinfunction "2_2") (pintype "passive"))
      (node (ref "C272") (pin "2") (pinfunction "2_2") (pintype "passive"))
      (node (ref "DA20") (pin "13") (pinfunction "EN_13") (pintype "passive"))
      (node (ref "DA20") (pin "15") (pinfunction "IN_15") (pintype "passive"))
      (node (ref "DA20") (pin "16") (pinfunction "IN_16") (pintype "passive"))
      (node (ref "L45") (pin "1") (pinfunction "1_1") (pintype "passive"))
    )
    (net (code "56") (name "Net-(DA20-NR)") (class "Default")
      (node (ref "C278") (pin "2") (pinfunction "2_2") (pintype "passive"))
      (node (ref "DA20") (pin "14") (pinfunction "NR_14") (pintype "passive"))
    )
    (net (code "57") (name "Net-(DA21-EN)") (class "Default")
      (node (ref "C284") (pin "2") (pinfunction "2_2") (pintype "passive"))
      (node (ref "C288") (pin "2") (pinfunction "2_2") (pintype "passive"))
      (node (ref "C291") (pin "2") (pinfunction "2_2") (pintype "passive"))
      (node (ref "DA21") (pin "13") (pinfunction "EN_13") (pintype "passive"))
      (node (ref "DA21") (pin "15") (pinfunction "IN_15") (pintype "passive"))
      (node (ref "DA21") (pin "16") (pinfunction "IN_16") (pintype "passive"))
      (node (ref "L47") (pin "2") (pinfunction "2_2") (pintype "passive"))
    )
    (net (code "58") (name "Net-(DA21-NR)") (class "Default")
      (node (ref "C292") (pin "2") (pinfunction "2_2") (pintype "passive"))
      (node (ref "DA21") (pin "14") (pinfunction "NR_14") (pintype "passive"))
    )
    (net (code "59") (name "Net-(DA21-SENSE)") (class "Default")
      (node (ref "C293") (pin "2") (pinfunction "2_2") (pintype "passive"))
      (node (ref "C294") (pin "2") (pinfunction "2_2") (pintype "passive"))
      (node (ref "C295") (pin "2") (pinfunction "2_2") (pintype "passive"))
      (node (ref "DA21") (pin "1") (pinfunction "OUT_1") (pintype "passive"))
      (node (ref "DA21") (pin "20") (pinfunction "OUT_20") (pintype "passive"))
      (node (ref "DA21") (pin "3") (pinfunction "SENSE_3") (pintype "passive"))
      (node (ref "DD12") (pin "56") (pinfunction "AVDD33_56") (pintype "passive"))
      (node (ref "DD12") (pin "57") (pinfunction "AVDD33_57") (pintype "passive"))
      (node (ref "DD12") (pin "71") (pinfunction "AVDD33_71") (pintype "passive"))
      (node (ref "DD12") (pin "72") (pinfunction "AVDD33_72") (pintype "passive"))
    )
    (net (code "60") (name "Net-(DD12-CSB)") (class "Default")
      (node (ref "C283") (pin "2") (pinfunction "2_2") (pintype "passive"))
      (node (ref "DD12") (pin "52") (pinfunction "CSB_52") (pintype "passive"))
      (node (ref "R140") (pin "2") (pinfunction "2_2") (pintype "passive"))
    )
    (net (code "61") (name "Net-(DD12-DVDD33)") (class "Default")
      (node (ref "C286") (pin "2") (pinfunction "2_2") (pintype "passive"))
      (node (ref "C289") (pin "2") (pinfunction "2_2") (pintype "passive"))
      (node (ref "DD12") (pin "27") (pinfunction "DVDD33_27") (pintype "passive"))
      (node (ref "L48") (pin "2") (pinfunction "2_2") (pintype "passive"))
    )
    (net (code "62") (name "Net-(DD12-FS_ADJ)") (class "Default")
      (node (ref "DD12") (pin "54") (pinfunction "FS_ADJ_54") (pintype "passive"))
      (node (ref "R146") (pin "1") (pinfunction "1_1") (pintype "passive"))
    )
    (net (code "63") (name "Net-(DD12-IOUT1N)") (class "Default")
      (node (ref "C296") (pin "2") (pinfunction "2_2") (pintype "passive"))
      (node (ref "DD12") (pin "68") (pinfunction "IOUT1N_68") (pintype "passive"))
      (node (ref "R147") (pin "1") (pinfunction "1_1") (pintype "passive"))
      (node (ref "R157") (pin "2") (pinfunction "2_2") (pintype "passive"))
      (node (ref "T5") (pin "3") (pinfunction "SECONDARY_3") (pintype "passive"))
    )
    (net (code "64") (name "Net-(DD12-IOUT1P)") (class "Default")
      (node (ref "C298") (pin "2") (pinfunction "2_2") (pintype "passive"))
      (node (ref "DD12") (pin "69") (pinfunction "IOUT1P_69") (pintype "passive"))
      (node (ref "R148") (pin "1") (pinfunction "1_1") (pintype "passive"))
      (node (ref "R153") (pin "2") (pinfunction "2_2") (pintype "passive"))
      (node (ref "T5") (pin "1") (pinfunction "SECONDARY_DOT_1") (pintype "passive"))
    )
    (net (code "65") (name "Net-(DD12-IOUT2N)") (class "Default")
      (node (ref "C301") (pin "2") (pinfunction "2_2") (pintype "passive"))
      (node (ref "DD12") (pin "60") (pinfunction "IOUT2N_60") (pintype "passive"))
      (node (ref "R149") (pin "1") (pinfunction "1_1") (pintype "passive"))
      (node (ref "R154") (pin "2") (pinfunction "2_2") (pintype "passive"))
      (node (ref "T4") (pin "3") (pinfunction "SECONDARY_3") (pintype "passive"))
    )
    (net (code "66") (name "Net-(DD12-IOUT2P)") (class "Default")
      (node (ref "C303") (pin "2") (pinfunction "2_2") (pintype "passive"))
      (node (ref "DD12") (pin "59") (pinfunction "IOUT2P_59") (pintype "passive"))
      (node (ref "R150") (pin "1") (pinfunction "1_1") (pintype "passive"))
      (node (ref "R152") (pin "2") (pinfunction "2_2") (pintype "passive"))
      (node (ref "T4") (pin "1") (pinfunction "SECONDARY_DOT_1") (pintype "passive"))
    )
    (net (code "67") (name "Net-(DD12-REFIO)") (class "Default")
      (node (ref "C290") (pin "2") (pinfunction "2_2") (pintype "passive"))
      (node (ref "DD12") (pin "55") (pinfunction "REFIO_55") (pintype "passive"))
    )
    (net (code "68") (name "Net-(DD12-RESET)") (class "Default")
      (node (ref "C287") (pin "2") (pinfunction "2_2") (pintype "passive"))
      (node (ref "DD12") (pin "53") (pinfunction "RESET_53") (pintype "passive"))
      (node (ref "R139") (pin "2") (pinfunction "2_2") (pintype "passive"))
    )
    (net (code "69") (name "Net-(DD12-SCLK)") (class "Default")
      (node (ref "C281") (pin "2") (pinfunction "2_2") (pintype "passive"))
      (node (ref "DD12") (pin "51") (pinfunction "SCLK_51") (pintype "passive"))
      (node (ref "R141") (pin "2") (pinfunction "2_2") (pintype "passive"))
    )
    (net (code "70") (name "Net-(DD12-SDIO)") (class "Default")
      (node (ref "C279") (pin "2") (pinfunction "2_2") (pintype "passive"))
      (node (ref "DD12") (pin "50") (pinfunction "SDIO_50") (pintype "passive"))
      (node (ref "R142") (pin "2") (pinfunction "2_2") (pintype "passive"))
    )
    (net (code "71") (name "Net-(DD12-SDO)") (class "Default")
      (node (ref "C277") (pin "2") (pinfunction "2_2") (pintype "passive"))
      (node (ref "DD12") (pin "49") (pinfunction "SDO_49") (pintype "passive"))
      (node (ref "R143") (pin "2") (pinfunction "2_2") (pintype "passive"))
    )
    (net (code "72") (name "Net-(T3-PRIMARY_DOT)") (class "Default")
      (node (ref "C306") (pin "2") (pinfunction "2_2") (pintype "passive"))
      (node (ref "C307") (pin "2") (pinfunction "2_2") (pintype "passive"))
      (node (ref "L50") (pin "1") (pinfunction "1_1") (pintype "passive"))
      (node (ref "T3") (pin "5") (pinfunction "PRIMARY_DOT_5") (pintype "passive"))
    )
    (net (code "73") (name "Net-(T3-SECONDARY)") (class "Default")
      (node (ref "R154") (pin "1") (pinfunction "1_1") (pintype "passive"))
      (node (ref "R157") (pin "1") (pinfunction "1_1") (pintype "passive"))
      (node (ref "T3") (pin "3") (pinfunction "SECONDARY_3") (pintype "passive"))
    )
    (net (code "74") (name "Net-(T3-SECONDARY_DOT)") (class "Default")
      (node (ref "R152") (pin "1") (pinfunction "1_1") (pintype "passive"))
      (node (ref "R153") (pin "1") (pinfunction "1_1") (pintype "passive"))
      (node (ref "T3") (pin "1") (pinfunction "SECONDARY_DOT_1") (pintype "passive"))
    )
    (net (code "75") (name "Net-(T4-PRIMARY_DOT)") (class "Default")
      (node (ref "C308") (pin "2") (pinfunction "2_2") (pintype "passive"))
      (node (ref "C312") (pin "2") (pinfunction "2_2") (pintype "passive"))
      (node (ref "L51") (pin "1") (pinfunction "1_1") (pintype "passive"))
      (node (ref "T4") (pin "5") (pinfunction "PRIMARY_DOT_5") (pintype "passive"))
    )
    (net (code "76") (name "Net-(T5-PRIMARY_DOT)") (class "Default")
      (node (ref "C309") (pin "2") (pinfunction "2_2") (pintype "passive"))
      (node (ref "C313") (pin "2") (pinfunction "2_2") (pintype "passive"))
      (node (ref "L52") (pin "1") (pinfunction "1_1") (pintype "passive"))
      (node (ref "T5") (pin "5") (pinfunction "PRIMARY_DOT_5") (pintype "passive"))
    )
    (net (code "77") (name "VDD_1V8") (class "Default")
      (node (ref "L46") (pin "1") (pinfunction "1_1") (pintype "passive"))
    )
    (net (code "78") (name "VDD_3V3") (class "Default")
      (node (ref "L48") (pin "1") (pinfunction "1_1") (pintype "passive"))
    )
    (net (code "79") (name "unconnected-(DA20-0P1V-Pad12)") (class "Default")
      (node (ref "DA20") (pin "12") (pinfunction "0P1V_12") (pintype "passive"))
    )
    (net (code "80") (name "unconnected-(DA20-0P2V-Pad11)") (class "Default")
      (node (ref "DA20") (pin "11") (pinfunction "0P2V_11") (pintype "passive"))
    )
    (net (code "81") (name "unconnected-(DA20-0P8V-Pad9)") (class "Default")
      (node (ref "DA20") (pin "9") (pinfunction "0P8V_9") (pintype "passive"))
    )
    (net (code "82") (name "unconnected-(DA20-1P6V-Pad8)") (class "Default")
      (node (ref "DA20") (pin "8") (pinfunction "1P6V_8") (pintype "passive"))
    )
    (net (code "83") (name "unconnected-(DA20-3P2V-Pad6)") (class "Default")
      (node (ref "DA20") (pin "6") (pinfunction "3P2V_6") (pintype "passive"))
    )
    (net (code "84") (name "unconnected-(DA20-6P4V1-Pad5)") (class "Default")
      (node (ref "DA20") (pin "5") (pinfunction "6P4V1_5") (pintype "passive"))
    )
    (net (code "85") (name "unconnected-(DA20-6P4V2-Pad4)") (class "Default")
      (node (ref "DA20") (pin "4") (pinfunction "6P4V2_4") (pintype "passive"))
    )
    (net (code "86") (name "unconnected-(DA21-0P4V-Pad10)") (class "Default")
      (node (ref "DA21") (pin "10") (pinfunction "0P4V_10") (pintype "passive"))
    )
    (net (code "87") (name "unconnected-(DA21-0P8V-Pad9)") (class "Default")
      (node (ref "DA21") (pin "9") (pinfunction "0P8V_9") (pintype "passive"))
    )
    (net (code "88") (name "unconnected-(DA21-3P2V-Pad6)") (class "Default")
      (node (ref "DA21") (pin "6") (pinfunction "3P2V_6") (pintype "passive"))
    )
    (net (code "89") (name "unconnected-(DA21-6P4V1-Pad5)") (class "Default")
      (node (ref "DA21") (pin "5") (pinfunction "6P4V1_5") (pintype "passive"))
    )
    (net (code "90") (name "unconnected-(DA21-6P4V2-Pad4)") (class "Default")
      (node (ref "DA21") (pin "4") (pinfunction "6P4V2_4") (pintype "passive"))
    )
    (net (code "91") (name "unconnected-(DD12-AUX1N-Pad65)") (class "Default")
      (node (ref "DD12") (pin "65") (pinfunction "AUX1N_65") (pintype "passive"))
    )
    (net (code "92") (name "unconnected-(DD12-AUX1P-Pad66)") (class "Default")
      (node (ref "DD12") (pin "66") (pinfunction "AUX1P_66") (pintype "passive"))
    )
    (net (code "93") (name "unconnected-(DD12-AUX2N-Pad63)") (class "Default")
      (node (ref "DD12") (pin "63") (pinfunction "AUX2N_63") (pintype "passive"))
    )
    (net (code "94") (name "unconnected-(DD12-AUX2P-Pad62)") (class "Default")
      (node (ref "DD12") (pin "62") (pinfunction "AUX2P_62") (pintype "passive"))
    )
  )
)
